# Zavrsni_rad.net
KiCad netlist of a schematic drawn in EasyEDA
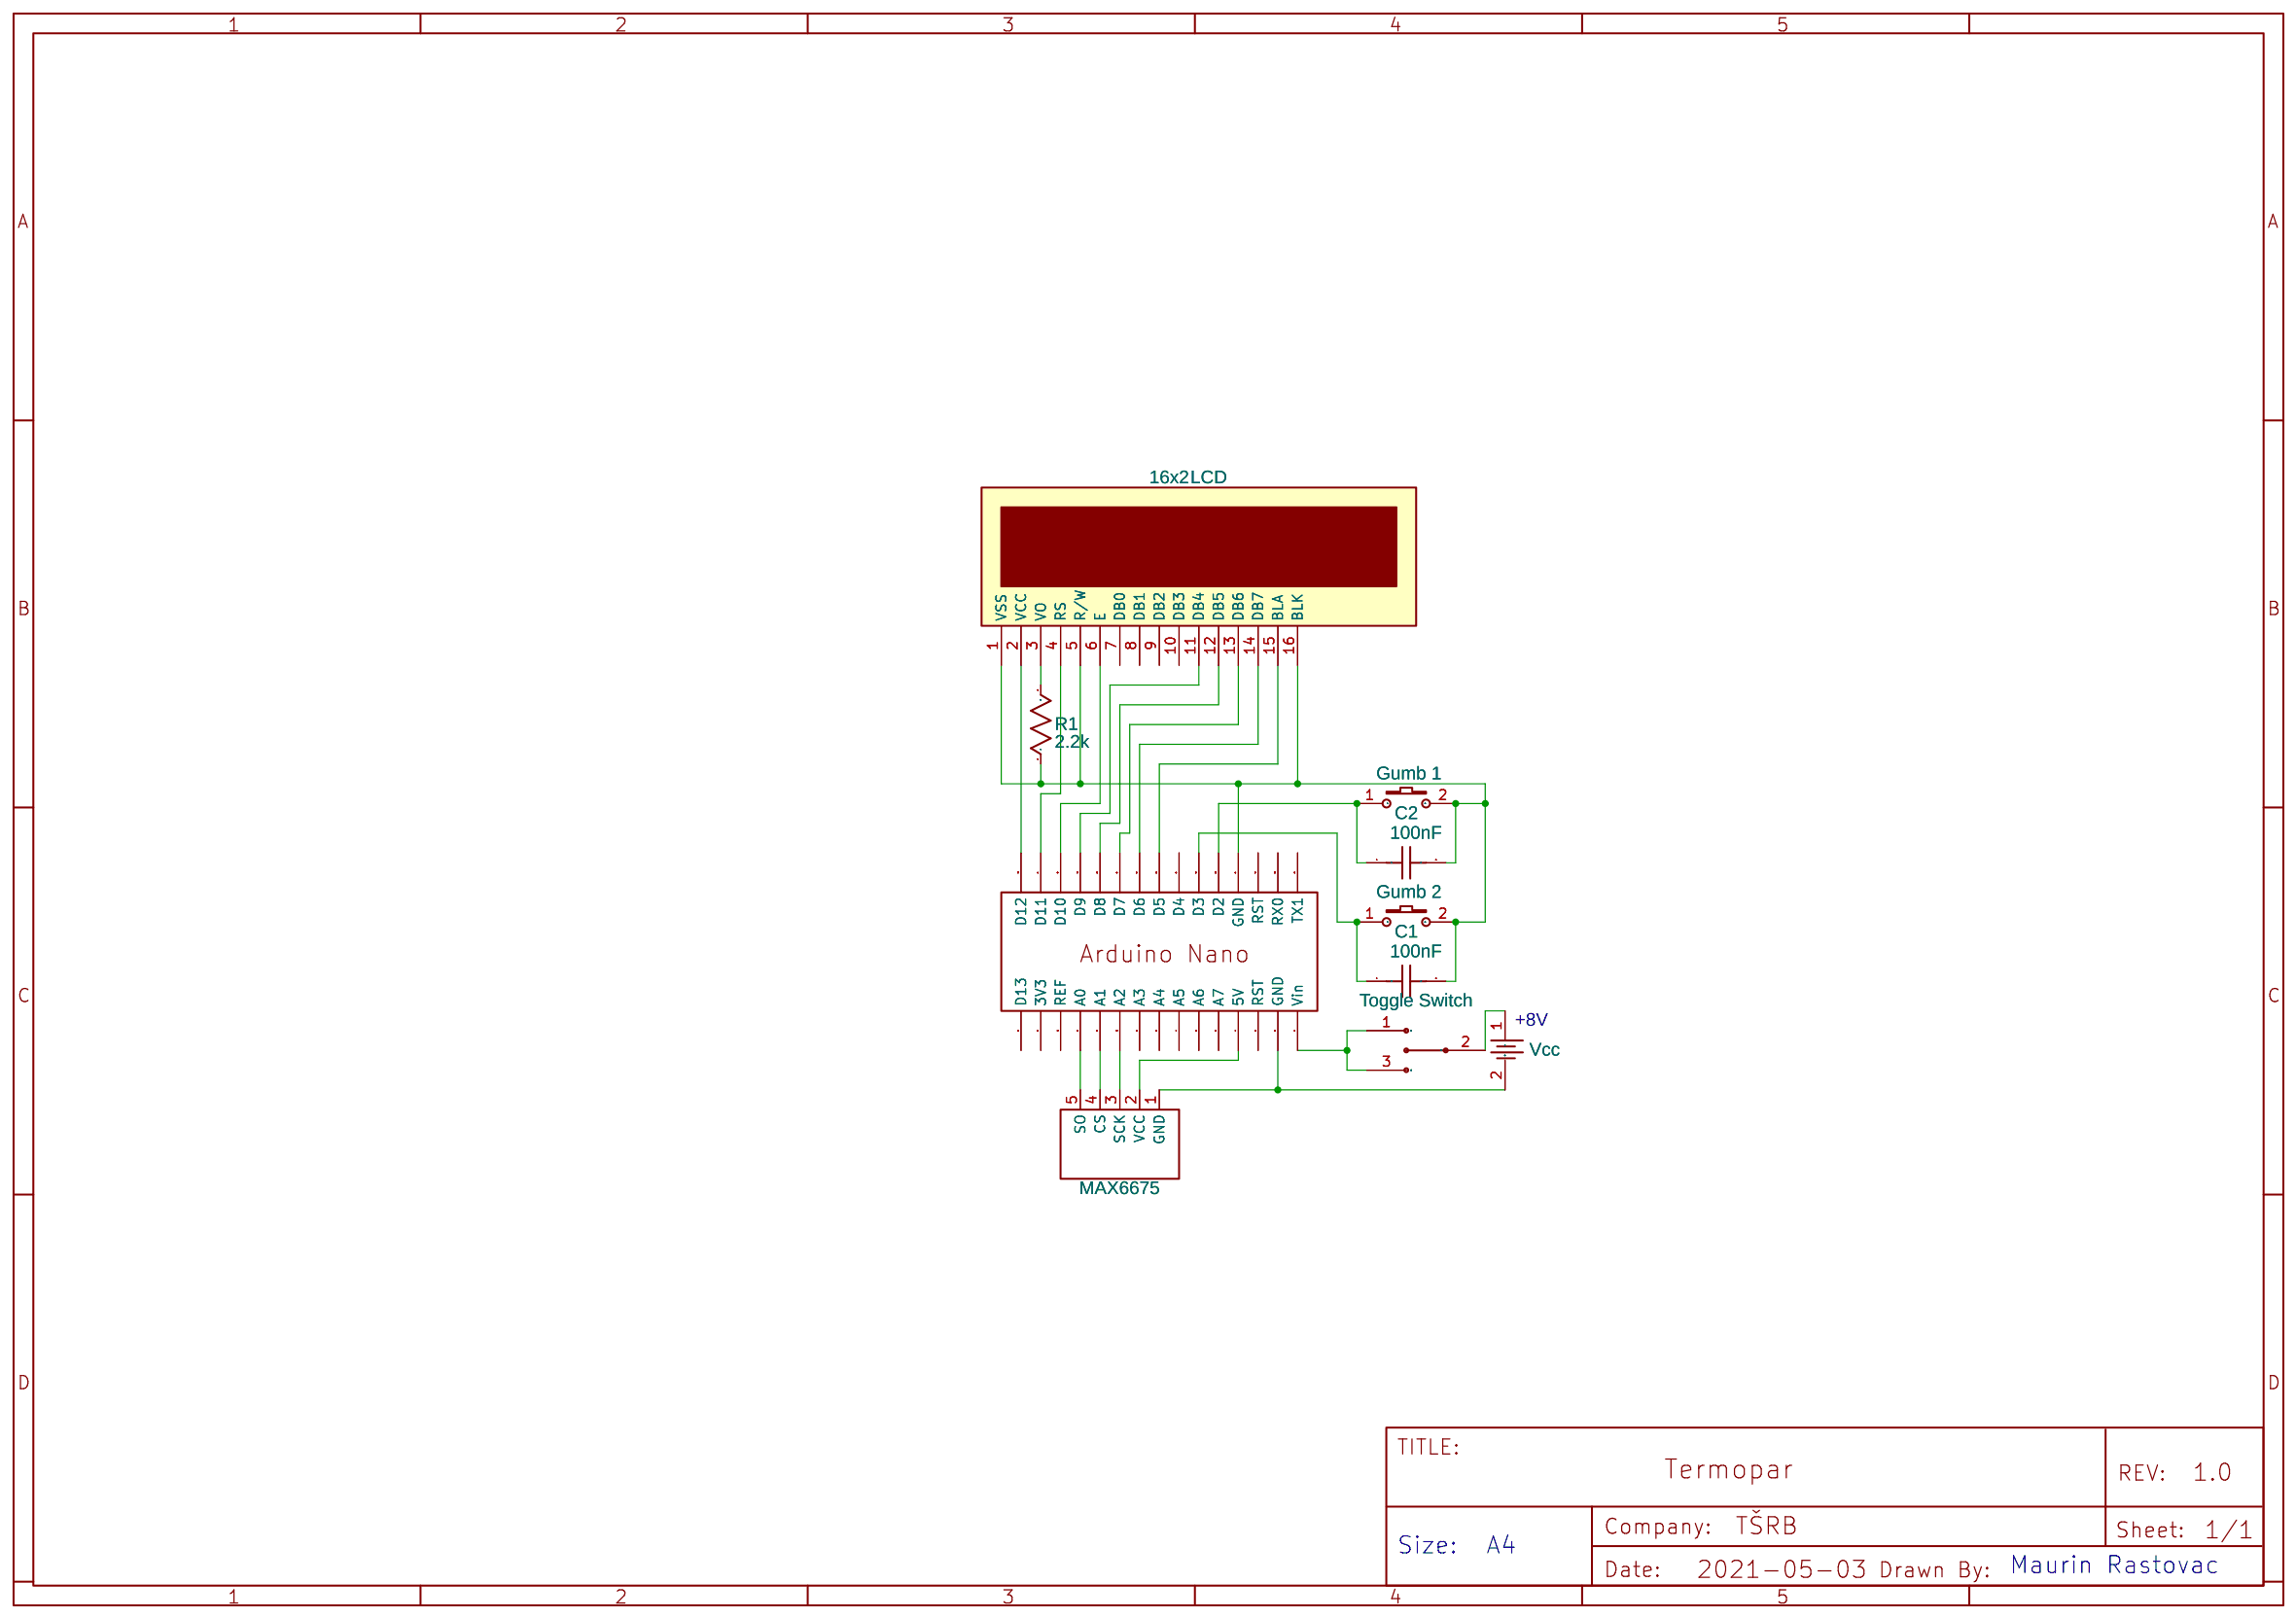
[diagram p0: schematic sheet]

(export (version "E")
  (design (tool "Eeschema 10.0.6"))
  (components
    (comp (ref "B1")
      (value "Vcc")
      (fields (field (name "BOM_Manufacturer Part") "CR1220-2") (field (name "BOM_Supplier Part") "C70381"))
      (libsource (lib "") (part "CR1220-2"))
    )
    (comp (ref "C1") (value "100nF") (libsource (lib "") (part "C_0603_US")))
    (comp (ref "C2") (value "100nF") (libsource (lib "") (part "C_0603_US")))
    (comp (ref "KEY2")
      (value "Gumb 2")
      (fields
        (field (name "BOM_Manufacturer Part") "K2-1107ST-A4SW-06")
        (field (name "BOM_Supplier Part") "C118141")
      )
      (libsource (lib "") (part "K2-3.6×6.1_SMD"))
    )
    (comp (ref "KEY3")
      (value "Gumb 1")
      (fields
        (field (name "BOM_Manufacturer Part") "K2-1107ST-A4SW-06")
        (field (name "BOM_Supplier Part") "C118141")
      )
      (libsource (lib "") (part "K2-3.6×6.1_SMD"))
    )
    (comp (ref "LCD")
      (value "16x2")
      (fields
        (field (name "BOM_Manufacturer Part") "LCM1602K-NSW-BBW")
        (field (name "BOM_Supplier Part") "C83275")
      )
      (libsource (lib "") (part "LCD1602"))
    )
    (comp (ref "M1")
      (value "Arduino_Nano_2")
      (fields (field (name "BOM_Manufacturer Part") "Arduino Nano"))
      (libsource (lib "") (part "Arduino_Nano_2"))
    )
    (comp (ref "P1")
      (value "MAX6675")
      (fields
        (field (name "BOM_Manufacturer Part") "Female headerHDR1X8-2.54")
        (field (name "BOM_Supplier Part") "C27438")
      )
      (libsource (lib "") (part "MAX6675-MODULE"))
    )
    (comp (ref "R1") (value "2.2k") (libsource (lib "") (part "R_0603_US")))
    (comp (ref "U1") (value "Toggle Switch") (libsource (lib "") (part "Toggle Switch")))
  )
  (nets
    (net (code "1") (name "Net-(B1-Pad1)") (class "Default")
      (node (ref "B1") (pin "1") (pinfunction "1_1") (pintype "input"))
      (node (ref "U1") (pin "2") (pinfunction "2_2") (pintype "unspecified"))
    )
    (net (code "2") (name "Net-(LCD-BLA)") (class "Default")
      (node (ref "LCD") (pin "15") (pinfunction "BLA_15") (pintype "unspecified"))
      (node (ref "M1") (pin "23") (pinfunction "D5_23") (pintype "unspecified"))
    )
    (net (code "3") (name "Net-(LCD-BLK)") (class "Default")
      (node (ref "C1") (pin "2") (pinfunction "2_2") (pintype "unspecified"))
      (node (ref "C2") (pin "2") (pinfunction "2_2") (pintype "unspecified"))
      (node (ref "KEY2") (pin "2") (pinfunction "2_2") (pintype "unspecified"))
      (node (ref "KEY3") (pin "2") (pinfunction "2_2") (pintype "unspecified"))
      (node (ref "LCD") (pin "1") (pinfunction "VSS_1") (pintype "unspecified"))
      (node (ref "LCD") (pin "16") (pinfunction "BLK_16") (pintype "unspecified"))
      (node (ref "LCD") (pin "5") (pinfunction "R/W_5") (pintype "unspecified"))
      (node (ref "M1") (pin "27") (pinfunction "GND_27") (pintype "unspecified"))
      (node (ref "R1") (pin "1") (pinfunction "1_1") (pintype "unspecified"))
    )
    (net (code "4") (name "Net-(LCD-DB4)") (class "Default")
      (node (ref "LCD") (pin "11") (pinfunction "DB4_11") (pintype "unspecified"))
      (node (ref "M1") (pin "19") (pinfunction "D9_19") (pintype "unspecified"))
    )
    (net (code "5") (name "Net-(LCD-DB5)") (class "Default")
      (node (ref "LCD") (pin "12") (pinfunction "DB5_12") (pintype "unspecified"))
      (node (ref "M1") (pin "20") (pinfunction "D8_20") (pintype "unspecified"))
    )
    (net (code "6") (name "Net-(LCD-DB6)") (class "Default")
      (node (ref "LCD") (pin "13") (pinfunction "DB6_13") (pintype "unspecified"))
      (node (ref "M1") (pin "21") (pinfunction "D7_21") (pintype "unspecified"))
    )
    (net (code "7") (name "Net-(LCD-DB7)") (class "Default")
      (node (ref "LCD") (pin "14") (pinfunction "DB7_14") (pintype "unspecified"))
      (node (ref "M1") (pin "22") (pinfunction "D6_22") (pintype "unspecified"))
    )
    (net (code "8") (name "Net-(LCD-E)") (class "Default")
      (node (ref "LCD") (pin "6") (pinfunction "E_6") (pintype "unspecified"))
      (node (ref "M1") (pin "18") (pinfunction "D10_18") (pintype "unspecified"))
    )
    (net (code "9") (name "Net-(LCD-RS)") (class "Default")
      (node (ref "LCD") (pin "4") (pinfunction "RS_4") (pintype "unspecified"))
      (node (ref "M1") (pin "17") (pinfunction "D11_17") (pintype "unspecified"))
    )
    (net (code "10") (name "Net-(LCD-VCC)") (class "Default")
      (node (ref "LCD") (pin "2") (pinfunction "VCC_2") (pintype "unspecified"))
      (node (ref "M1") (pin "16") (pinfunction "D12_16") (pintype "unspecified"))
    )
    (net (code "11") (name "Net-(LCD-VO)") (class "Default")
      (node (ref "LCD") (pin "3") (pinfunction "VO_3") (pintype "unspecified"))
      (node (ref "R1") (pin "2") (pinfunction "2_2") (pintype "unspecified"))
    )
    (net (code "12") (name "Net-(M1-5V)") (class "Default")
      (node (ref "M1") (pin "4") (pinfunction "5V_4") (pintype "unspecified"))
      (node (ref "P1") (pin "2") (pinfunction "VCC_2") (pintype "input"))
    )
    (net (code "13") (name "Net-(M1-A0)") (class "Default")
      (node (ref "M1") (pin "12") (pinfunction "A0_12") (pintype "unspecified"))
      (node (ref "P1") (pin "5") (pinfunction "SO_5") (pintype "input"))
    )
    (net (code "14") (name "Net-(M1-A1)") (class "Default")
      (node (ref "M1") (pin "11") (pinfunction "A1_11") (pintype "unspecified"))
      (node (ref "P1") (pin "4") (pinfunction "CS_4") (pintype "input"))
    )
    (net (code "15") (name "Net-(M1-A2)") (class "Default")
      (node (ref "M1") (pin "10") (pinfunction "A2_10") (pintype "unspecified"))
      (node (ref "P1") (pin "3") (pinfunction "SCK_3") (pintype "input"))
    )
    (net (code "16") (name "Net-(M1-D2)") (class "Default")
      (node (ref "C2") (pin "1") (pinfunction "1_1") (pintype "unspecified"))
      (node (ref "KEY3") (pin "1") (pinfunction "1_1") (pintype "unspecified"))
      (node (ref "M1") (pin "26") (pinfunction "D2_26") (pintype "unspecified"))
    )
    (net (code "17") (name "Net-(M1-D3)") (class "Default")
      (node (ref "C1") (pin "1") (pinfunction "1_1") (pintype "unspecified"))
      (node (ref "KEY2") (pin "1") (pinfunction "1_1") (pintype "unspecified"))
      (node (ref "M1") (pin "25") (pinfunction "D3_25") (pintype "unspecified"))
    )
    (net (code "18") (name "Net-(M1-Vin)") (class "Default")
      (node (ref "M1") (pin "1") (pinfunction "Vin_1") (pintype "unspecified"))
      (node (ref "U1") (pin "1") (pinfunction "1_1") (pintype "unspecified"))
      (node (ref "U1") (pin "3") (pinfunction "3_3") (pintype "unspecified"))
    )
    (net (code "19") (name "Net-(P1-GND)") (class "Default")
      (node (ref "B1") (pin "2") (pinfunction "2_2") (pintype "input"))
      (node (ref "M1") (pin "2") (pinfunction "GND_2") (pintype "unspecified"))
      (node (ref "P1") (pin "1") (pinfunction "GND_1") (pintype "input"))
    )
    (net (code "20") (name "unconnected-(LCD-DB0-Pad7)") (class "Default")
      (node (ref "LCD") (pin "7") (pinfunction "DB0_7") (pintype "unspecified"))
    )
    (net (code "21") (name "unconnected-(LCD-DB1-Pad8)") (class "Default")
      (node (ref "LCD") (pin "8") (pinfunction "DB1_8") (pintype "unspecified"))
    )
    (net (code "22") (name "unconnected-(LCD-DB2-Pad9)") (class "Default")
      (node (ref "LCD") (pin "9") (pinfunction "DB2_9") (pintype "unspecified"))
    )
    (net (code "23") (name "unconnected-(LCD-DB3-Pad10)") (class "Default")
      (node (ref "LCD") (pin "10") (pinfunction "DB3_10") (pintype "unspecified"))
    )
    (net (code "24") (name "unconnected-(M1-3V3-Pad14)") (class "Default")
      (node (ref "M1") (pin "14") (pinfunction "3V3_14") (pintype "unspecified"))
    )
    (net (code "25") (name "unconnected-(M1-A3-Pad9)") (class "Default")
      (node (ref "M1") (pin "9") (pinfunction "A3_9") (pintype "unspecified"))
    )
    (net (code "26") (name "unconnected-(M1-A4-Pad8)") (class "Default")
      (node (ref "M1") (pin "8") (pinfunction "A4_8") (pintype "unspecified"))
    )
    (net (code "27") (name "unconnected-(M1-A5-Pad7)") (class "Default")
      (node (ref "M1") (pin "7") (pinfunction "A5_7") (pintype "unspecified"))
    )
    (net (code "28") (name "unconnected-(M1-A6-Pad6)") (class "Default")
      (node (ref "M1") (pin "6") (pinfunction "A6_6") (pintype "unspecified"))
    )
    (net (code "29") (name "unconnected-(M1-A7-Pad5)") (class "Default")
      (node (ref "M1") (pin "5") (pinfunction "A7_5") (pintype "unspecified"))
    )
    (net (code "30") (name "unconnected-(M1-D4-Pad24)") (class "Default")
      (node (ref "M1") (pin "24") (pinfunction "D4_24") (pintype "unspecified"))
    )
    (net (code "31") (name "unconnected-(M1-D13-Pad15)") (class "Default")
      (node (ref "M1") (pin "15") (pinfunction "D13_15") (pintype "unspecified"))
    )
    (net (code "32") (name "unconnected-(M1-REF-Pad13)") (class "Default")
      (node (ref "M1") (pin "13") (pinfunction "REF_13") (pintype "unspecified"))
    )
    (net (code "33") (name "unconnected-(M1-RST-Pad3)") (class "Default")
      (node (ref "M1") (pin "3") (pinfunction "RST_3") (pintype "unspecified"))
    )
    (net (code "34") (name "unconnected-(M1-RST-Pad28)") (class "Default")
      (node (ref "M1") (pin "28") (pinfunction "RST_28") (pintype "unspecified"))
    )
    (net (code "35") (name "unconnected-(M1-RX0-Pad29)") (class "Default")
      (node (ref "M1") (pin "29") (pinfunction "RX0_29") (pintype "unspecified"))
    )
    (net (code "36") (name "unconnected-(M1-TX1-Pad30)") (class "Default")
      (node (ref "M1") (pin "30") (pinfunction "TX1_30") (pintype "unspecified"))
    )
  )
)
